# me433mtc.net
KiCad netlist of a schematic drawn in EAGLE
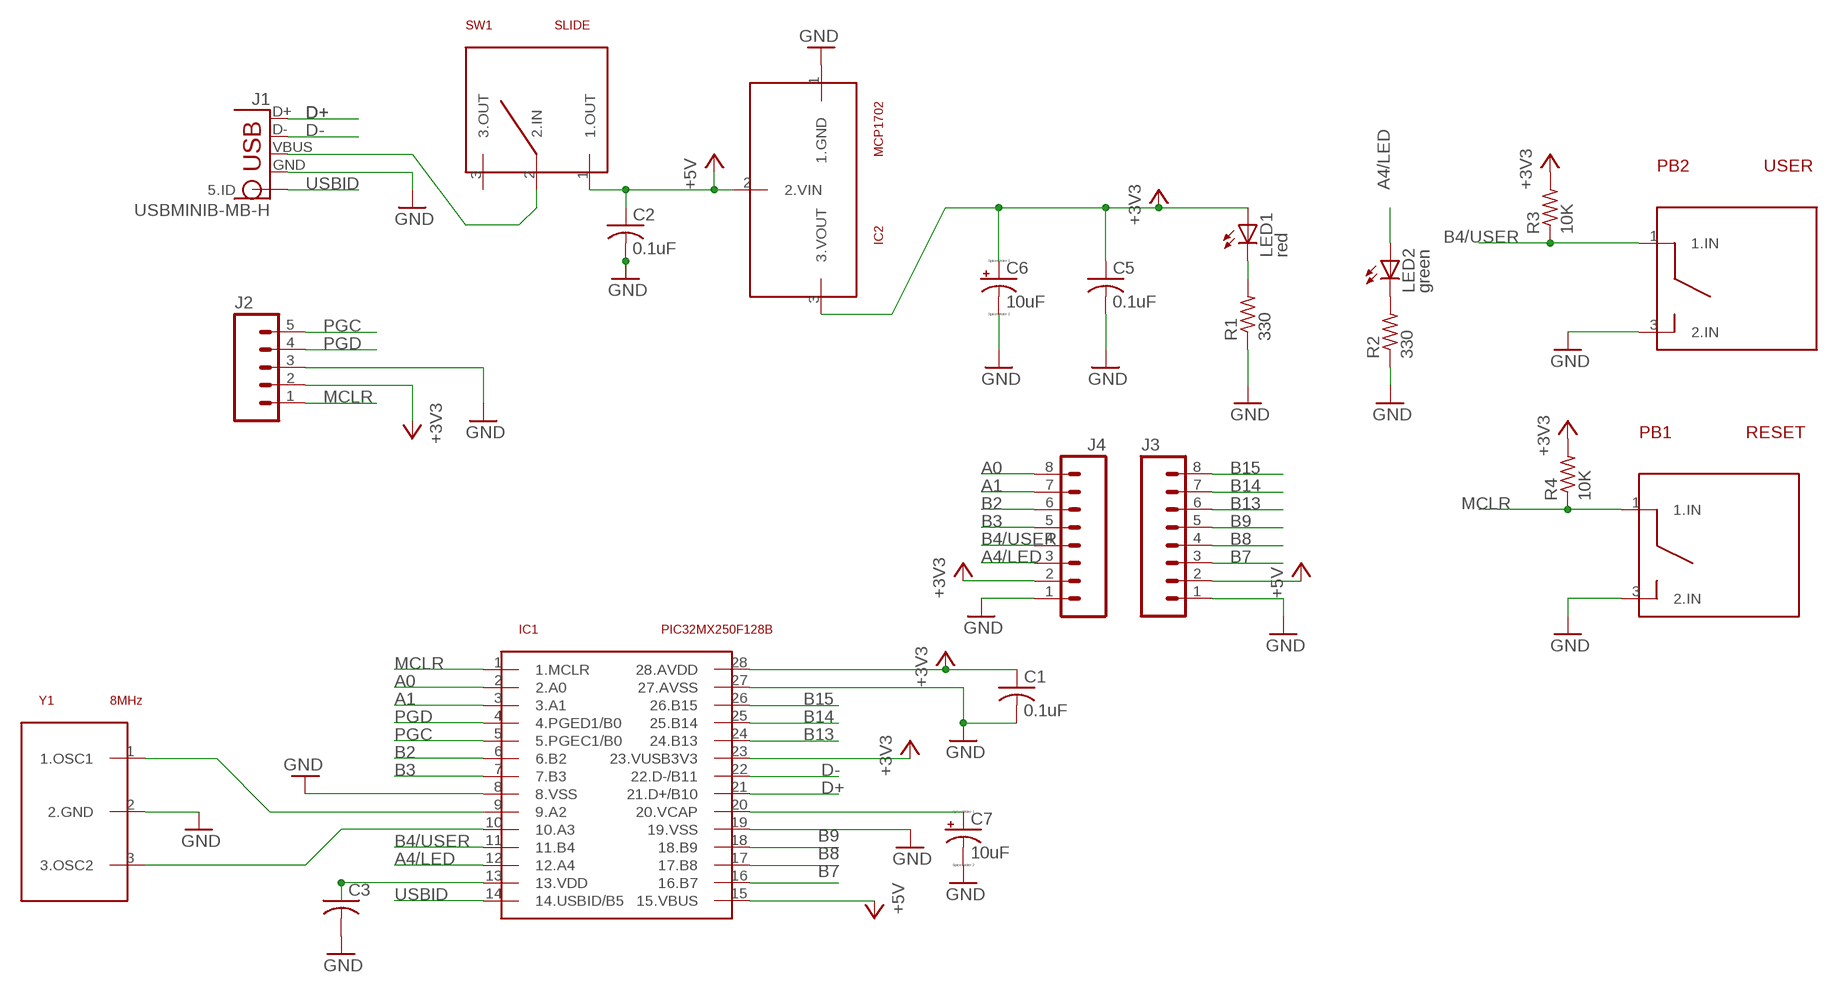
[diagram p0: schematic, sheet 1]

(export (version "E")
  (design (tool "Eeschema 10.0.6"))
  (components
    (comp (ref "C1")
      (value "0.1uF")
      (footprint "eagle-import:C025-025X050")
      (libsource (lib "eagle-import") (part "C-US025-025X050"))
    )
    (comp (ref "C2")
      (value "0.1uF")
      (footprint "eagle-import:C025-025X050")
      (libsource (lib "eagle-import") (part "C-US025-025X050"))
    )
    (comp (ref "C3")
      (value "C-US025-025X050")
      (footprint "eagle-import:C025-025X050")
      (libsource (lib "eagle-import") (part "C-US025-025X050"))
    )
    (comp (ref "C5")
      (value "0.1uF")
      (footprint "eagle-import:C025-025X050")
      (libsource (lib "eagle-import") (part "C-US025-025X050"))
    )
    (comp (ref "C6")
      (value "10uF")
      (footprint "eagle-import:B45181B")
      (libsource (lib "eagle-import") (part "CPOL-USB45181B"))
    )
    (comp (ref "C7")
      (value "10uF")
      (footprint "eagle-import:B45181B")
      (libsource (lib "eagle-import") (part "CPOL-USB45181B"))
    )
    (comp (ref "IC1")
      (value "PIC32MX250F128B")
      (footprint "eagle-import:DIL28-3")
      (libsource (lib "eagle-import") (part "PIC32"))
    )
    (comp (ref "IC2")
      (value "MCP1702")
      (footprint "eagle-import:TO92")
      (libsource (lib "eagle-import") (part "MCP1702"))
    )
    (comp (ref "J1")
      (value "USBMINIB-MB-H")
      (footprint "eagle-import:USB-MB-H")
      (libsource (lib "eagle-import") (part "USBMINIB-MB-H"))
    )
    (comp (ref "J2")
      (value "M05PTH")
      (footprint "eagle-import:1X05")
      (libsource (lib "eagle-import") (part "M05PTH"))
    )
    (comp (ref "J3")
      (value "M08")
      (footprint "eagle-import:1X08_ROUND")
      (libsource (lib "eagle-import") (part "M08"))
    )
    (comp (ref "J4")
      (value "M08")
      (footprint "eagle-import:1X08_ROUND")
      (libsource (lib "eagle-import") (part "M08"))
    )
    (comp (ref "LED1")
      (value "red")
      (footprint "eagle-import:LED3MM")
      (libsource (lib "eagle-import") (part "LED3MM"))
    )
    (comp (ref "LED2")
      (value "green")
      (footprint "eagle-import:LED3MM")
      (libsource (lib "eagle-import") (part "LED3MM"))
    )
    (comp (ref "PB1")
      (value "RESET")
      (footprint "eagle-import:1X03")
      (libsource (lib "eagle-import") (part "BUTTON"))
    )
    (comp (ref "PB2")
      (value "USER")
      (footprint "eagle-import:1X03")
      (libsource (lib "eagle-import") (part "BUTTON"))
    )
    (comp (ref "R1")
      (value "330")
      (footprint "eagle-import:0204_7")
      (libsource (lib "eagle-import") (part "R-US_0204/7"))
    )
    (comp (ref "R2")
      (value "330")
      (footprint "eagle-import:0204_7")
      (libsource (lib "eagle-import") (part "R-US_0204/7"))
    )
    (comp (ref "R3")
      (value "10K")
      (footprint "eagle-import:0204_7")
      (libsource (lib "eagle-import") (part "R-US_0204/7"))
    )
    (comp (ref "R4")
      (value "10K")
      (footprint "eagle-import:0204_7")
      (libsource (lib "eagle-import") (part "R-US_0204/7"))
    )
    (comp (ref "SW1")
      (value "SLIDE")
      (footprint "eagle-import:1X03")
      (libsource (lib "eagle-import") (part "SLIDE"))
    )
    (comp (ref "Y1")
      (value "8MHz")
      (footprint "eagle-import:1X03")
      (libsource (lib "eagle-import") (part "RESONATOR"))
    )
  )
  (nets
    (net (code "1") (name "+3V3") (class "Default")
      (node (ref "C1") (pin "1") (pinfunction "1_1") (pintype "passive"))
      (node (ref "C3") (pin "1") (pinfunction "1_1") (pintype "passive"))
      (node (ref "C5") (pin "1") (pinfunction "1_1") (pintype "passive"))
      (node (ref "C6") (pin "+") (pinfunction "+_+") (pintype "passive"))
      (node (ref "IC1") (pin "13") (pinfunction "13.VDD_13") (pintype "bidirectional"))
      (node (ref "IC1") (pin "23") (pinfunction "23.VUSB3V3_23") (pintype "bidirectional"))
      (node (ref "IC1") (pin "28") (pinfunction "28.AVDD_28") (pintype "bidirectional"))
      (node (ref "IC2") (pin "3") (pinfunction "3.VOUT_3") (pintype "bidirectional"))
      (node (ref "J2") (pin "2") (pinfunction "2_2") (pintype "passive"))
      (node (ref "J4") (pin "2") (pinfunction "2_2") (pintype "passive"))
      (node (ref "LED1") (pin "A") (pinfunction "A_A") (pintype "passive"))
      (node (ref "R3") (pin "2") (pinfunction "2_2") (pintype "passive"))
      (node (ref "R4") (pin "2") (pinfunction "2_2") (pintype "passive"))
    )
    (net (code "2") (name "+5V") (class "Default")
      (node (ref "C2") (pin "1") (pinfunction "1_1") (pintype "passive"))
      (node (ref "IC1") (pin "15") (pinfunction "15.VBUS_15") (pintype "bidirectional"))
      (node (ref "IC2") (pin "2") (pinfunction "2.VIN_2") (pintype "bidirectional"))
      (node (ref "J3") (pin "2") (pinfunction "2_2") (pintype "passive"))
      (node (ref "SW1") (pin "1") (pinfunction "1.OUT_1") (pintype "bidirectional"))
    )
    (net (code "3") (name "/A0") (class "Default")
      (node (ref "IC1") (pin "2") (pinfunction "2.A0_2") (pintype "bidirectional"))
      (node (ref "J4") (pin "8") (pinfunction "A0_8") (pintype "passive"))
    )
    (net (code "4") (name "/A1") (class "Default")
      (node (ref "IC1") (pin "3") (pinfunction "3.A1_3") (pintype "bidirectional"))
      (node (ref "J4") (pin "7") (pinfunction "7_7") (pintype "passive"))
    )
    (net (code "5") (name "/A4{slash}LED") (class "Default")
      (node (ref "IC1") (pin "12") (pinfunction "12.A4_12") (pintype "bidirectional"))
      (node (ref "J4") (pin "3") (pinfunction "3_3") (pintype "passive"))
      (node (ref "LED2") (pin "A") (pinfunction "A_A") (pintype "passive"))
    )
    (net (code "6") (name "/B2") (class "Default")
      (node (ref "IC1") (pin "6") (pinfunction "6.B2_6") (pintype "bidirectional"))
      (node (ref "J4") (pin "6") (pinfunction "6_6") (pintype "passive"))
    )
    (net (code "7") (name "/B3") (class "Default")
      (node (ref "IC1") (pin "7") (pinfunction "7.B3_7") (pintype "bidirectional"))
      (node (ref "J4") (pin "5") (pinfunction "5_5") (pintype "passive"))
    )
    (net (code "8") (name "/B4{slash}USER") (class "Default")
      (node (ref "IC1") (pin "11") (pinfunction "11.B4_11") (pintype "bidirectional"))
      (node (ref "J4") (pin "4") (pinfunction "4_4") (pintype "passive"))
      (node (ref "PB2") (pin "1") (pinfunction "1.IN_1") (pintype "bidirectional"))
      (node (ref "R3") (pin "1") (pinfunction "1_1") (pintype "passive"))
    )
    (net (code "9") (name "/B7") (class "Default")
      (node (ref "IC1") (pin "16") (pinfunction "16.B7_16") (pintype "bidirectional"))
      (node (ref "J3") (pin "3") (pinfunction "3_3") (pintype "passive"))
    )
    (net (code "10") (name "/B8") (class "Default")
      (node (ref "IC1") (pin "17") (pinfunction "17.B8_17") (pintype "bidirectional"))
      (node (ref "J3") (pin "4") (pinfunction "4_4") (pintype "passive"))
    )
    (net (code "11") (name "/B9") (class "Default")
      (node (ref "IC1") (pin "18") (pinfunction "18.B9_18") (pintype "bidirectional"))
      (node (ref "J3") (pin "5") (pinfunction "5_5") (pintype "passive"))
    )
    (net (code "12") (name "/B13") (class "Default")
      (node (ref "IC1") (pin "24") (pinfunction "24.B13_24") (pintype "bidirectional"))
      (node (ref "J3") (pin "6") (pinfunction "6_6") (pintype "passive"))
    )
    (net (code "13") (name "/B14") (class "Default")
      (node (ref "IC1") (pin "25") (pinfunction "25.B14_25") (pintype "bidirectional"))
      (node (ref "J3") (pin "7") (pinfunction "7_7") (pintype "passive"))
    )
    (net (code "14") (name "/B15") (class "Default")
      (node (ref "IC1") (pin "26") (pinfunction "26.B15_26") (pintype "bidirectional"))
      (node (ref "J3") (pin "8") (pinfunction "A0_8") (pintype "passive"))
    )
    (net (code "15") (name "/D+") (class "Default")
      (node (ref "IC1") (pin "21") (pinfunction "21.D+/B10_21") (pintype "bidirectional"))
      (node (ref "J1") (pin "D+") (pinfunction "1.GND_D+") (pintype "bidirectional"))
    )
    (net (code "16") (name "/D-") (class "Default")
      (node (ref "IC1") (pin "22") (pinfunction "22.D-/B11_22") (pintype "bidirectional"))
      (node (ref "J1") (pin "D-") (pinfunction "2.ID_D-") (pintype "bidirectional"))
    )
    (net (code "17") (name "/MCLR") (class "Default")
      (node (ref "IC1") (pin "1") (pinfunction "1.MCLR_1") (pintype "bidirectional"))
      (node (ref "J2") (pin "1") (pinfunction "1_1") (pintype "passive"))
      (node (ref "PB1") (pin "1") (pinfunction "1.IN_1") (pintype "bidirectional"))
      (node (ref "R4") (pin "1") (pinfunction "1_1") (pintype "passive"))
    )
    (net (code "18") (name "/PGC") (class "Default")
      (node (ref "IC1") (pin "5") (pinfunction "5.PGEC1/B0_5") (pintype "bidirectional"))
      (node (ref "J2") (pin "5") (pinfunction "5_5") (pintype "passive"))
    )
    (net (code "19") (name "/PGD") (class "Default")
      (node (ref "IC1") (pin "4") (pinfunction "4.PGED1/B0_4") (pintype "bidirectional"))
      (node (ref "J2") (pin "4") (pinfunction "4_4") (pintype "passive"))
    )
    (net (code "20") (name "/USBID") (class "Default")
      (node (ref "IC1") (pin "14") (pinfunction "14.USBID/B5_14") (pintype "bidirectional"))
      (node (ref "J1") (pin "ID") (pinfunction "5.ID_ID") (pintype "bidirectional"))
    )
    (net (code "21") (name "GND") (class "Default")
      (node (ref "C1") (pin "2") (pinfunction "2_2") (pintype "passive"))
      (node (ref "C2") (pin "2") (pinfunction "2_2") (pintype "passive"))
      (node (ref "C3") (pin "2") (pinfunction "2_2") (pintype "passive"))
      (node (ref "C5") (pin "2") (pinfunction "2_2") (pintype "passive"))
      (node (ref "C6") (pin "-") (pinfunction "-_-") (pintype "passive"))
      (node (ref "C7") (pin "-") (pinfunction "-_-") (pintype "passive"))
      (node (ref "IC1") (pin "19") (pinfunction "19.VSS_19") (pintype "bidirectional"))
      (node (ref "IC1") (pin "27") (pinfunction "27.AVSS_27") (pintype "bidirectional"))
      (node (ref "IC1") (pin "8") (pinfunction "8.VSS_8") (pintype "bidirectional"))
      (node (ref "IC2") (pin "1") (pinfunction "1.GND_1") (pintype "bidirectional"))
      (node (ref "J1") (pin "GND") (pinfunction "4.D-_GND") (pintype "bidirectional"))
      (node (ref "J2") (pin "3") (pinfunction "3_3") (pintype "passive"))
      (node (ref "J3") (pin "1") (pinfunction "1_1") (pintype "passive"))
      (node (ref "J4") (pin "1") (pinfunction "1_1") (pintype "passive"))
      (node (ref "PB1") (pin "3") (pinfunction "2.IN_3") (pintype "bidirectional"))
      (node (ref "PB2") (pin "3") (pinfunction "2.IN_3") (pintype "bidirectional"))
      (node (ref "R1") (pin "1") (pinfunction "1_1") (pintype "passive"))
      (node (ref "R2") (pin "1") (pinfunction "1_1") (pintype "passive"))
      (node (ref "Y1") (pin "2") (pinfunction "2.GND_2") (pintype "bidirectional"))
    )
    (net (code "22") (name "Net-(IC1-9.A2)") (class "Default")
      (node (ref "IC1") (pin "9") (pinfunction "9.A2_9") (pintype "bidirectional"))
      (node (ref "Y1") (pin "1") (pinfunction "1.OSC1_1") (pintype "bidirectional"))
    )
    (net (code "23") (name "Net-(IC1-10.A3)") (class "Default")
      (node (ref "IC1") (pin "10") (pinfunction "10.A3_10") (pintype "bidirectional"))
      (node (ref "Y1") (pin "3") (pinfunction "3.OSC2_3") (pintype "bidirectional"))
    )
    (net (code "24") (name "Net-(IC1-20.VCAP)") (class "Default")
      (node (ref "C7") (pin "+") (pinfunction "+_+") (pintype "passive"))
      (node (ref "IC1") (pin "20") (pinfunction "20.VCAP_20") (pintype "bidirectional"))
    )
    (net (code "25") (name "Net-(J1-3.D+)") (class "Default")
      (node (ref "J1") (pin "VBUS") (pinfunction "3.D+_VBUS") (pintype "bidirectional"))
      (node (ref "SW1") (pin "2") (pinfunction "2.IN_2") (pintype "bidirectional"))
    )
    (net (code "26") (name "Net-(LED1-C)") (class "Default")
      (node (ref "LED1") (pin "K") (pinfunction "C_K") (pintype "passive"))
      (node (ref "R1") (pin "2") (pinfunction "2_2") (pintype "passive"))
    )
    (net (code "27") (name "Net-(LED2-C)") (class "Default")
      (node (ref "LED2") (pin "K") (pinfunction "C_K") (pintype "passive"))
      (node (ref "R2") (pin "2") (pinfunction "2_2") (pintype "passive"))
    )
    (net (code "28") (name "unconnected-(SW1-3.OUT-Pad3)") (class "Default")
      (node (ref "SW1") (pin "3") (pinfunction "3.OUT_3") (pintype "bidirectional"))
    )
  )
)
